# ConstantCurrentSupply_PNP_SCH.net
KiCad netlist of a schematic drawn in EAGLE
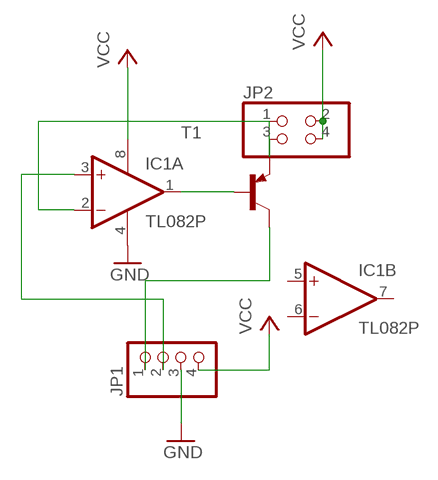
[diagram p0: schematic, sheet 1]

(export (version "E")
  (design (tool "Eeschema 10.0.6"))
  (components
    (comp (ref "IC1")
      (value "TL082P")
      (footprint "eagle-import:DIL08")
      (libsource (lib "eagle-import") (part "TL082P"))
    )
    (comp (ref "JP1")
      (value "PINHD-1X4")
      (footprint "eagle-import:1X04")
      (libsource (lib "eagle-import") (part "PINHD-1X4"))
    )
    (comp (ref "JP2")
      (value "PINHD-2X2")
      (footprint "eagle-import:2X02")
      (libsource (lib "eagle-import") (part "PINHD-2X2"))
    )
    (comp (ref "T1")
      (value "2N3906-PNP-TO92-EBC")
      (footprint "eagle-import:TO92-EBC")
      (libsource (lib "eagle-import") (part "-PNP-TO92-EBC2N3906"))
    )
  )
  (nets
    (net (code "1") (name "GND") (class "Default")
      (node (ref "IC1") (pin "4") (pinfunction "V-_4") (pintype "power_in"))
      (node (ref "JP1") (pin "3") (pinfunction "3_3") (pintype "passive"))
    )
    (net (code "2") (name "Net-(IC1A-+IN)") (class "Default")
      (node (ref "IC1") (pin "3") (pinfunction "+IN_3") (pintype "input"))
      (node (ref "JP1") (pin "2") (pinfunction "2_2") (pintype "passive"))
    )
    (net (code "3") (name "Net-(IC1A--IN)") (class "Default")
      (node (ref "IC1") (pin "2") (pinfunction "-IN_2") (pintype "input"))
      (node (ref "JP2") (pin "1") (pinfunction "1_1") (pintype "passive"))
      (node (ref "JP2") (pin "3") (pinfunction "3_3") (pintype "passive"))
      (node (ref "T1") (pin "E") (pinfunction "E_E") (pintype "passive"))
    )
    (net (code "4") (name "Net-(IC1A-OUT)") (class "Default")
      (node (ref "IC1") (pin "1") (pinfunction "OUT_1") (pintype "output"))
      (node (ref "T1") (pin "B") (pinfunction "B_B") (pintype "passive"))
    )
    (net (code "5") (name "Net-(JP1-Pad1)") (class "Default")
      (node (ref "JP1") (pin "1") (pinfunction "1_1") (pintype "passive"))
      (node (ref "T1") (pin "C") (pinfunction "C_C") (pintype "passive"))
    )
    (net (code "6") (name "VCC") (class "Default")
      (node (ref "IC1") (pin "8") (pinfunction "V+_8") (pintype "power_in"))
      (node (ref "JP1") (pin "4") (pinfunction "4_4") (pintype "passive"))
      (node (ref "JP2") (pin "2") (pinfunction "2_2") (pintype "passive"))
      (node (ref "JP2") (pin "4") (pinfunction "4_4") (pintype "passive"))
    )
    (net (code "7") (name "unconnected-(IC1B-+IN-Pad5)") (class "Default")
      (node (ref "IC1") (pin "5") (pinfunction "+IN_5") (pintype "input"))
    )
    (net (code "8") (name "unconnected-(IC1B--IN-Pad6)") (class "Default")
      (node (ref "IC1") (pin "6") (pinfunction "-IN_6") (pintype "input"))
    )
    (net (code "9") (name "unconnected-(IC1B-OUT-Pad7)") (class "Default")
      (node (ref "IC1") (pin "7") (pinfunction "OUT_7") (pintype "output"))
    )
  )
)
